# STM32_SCHEMATIC.net
KiCad netlist of a schematic drawn in Altium Designer
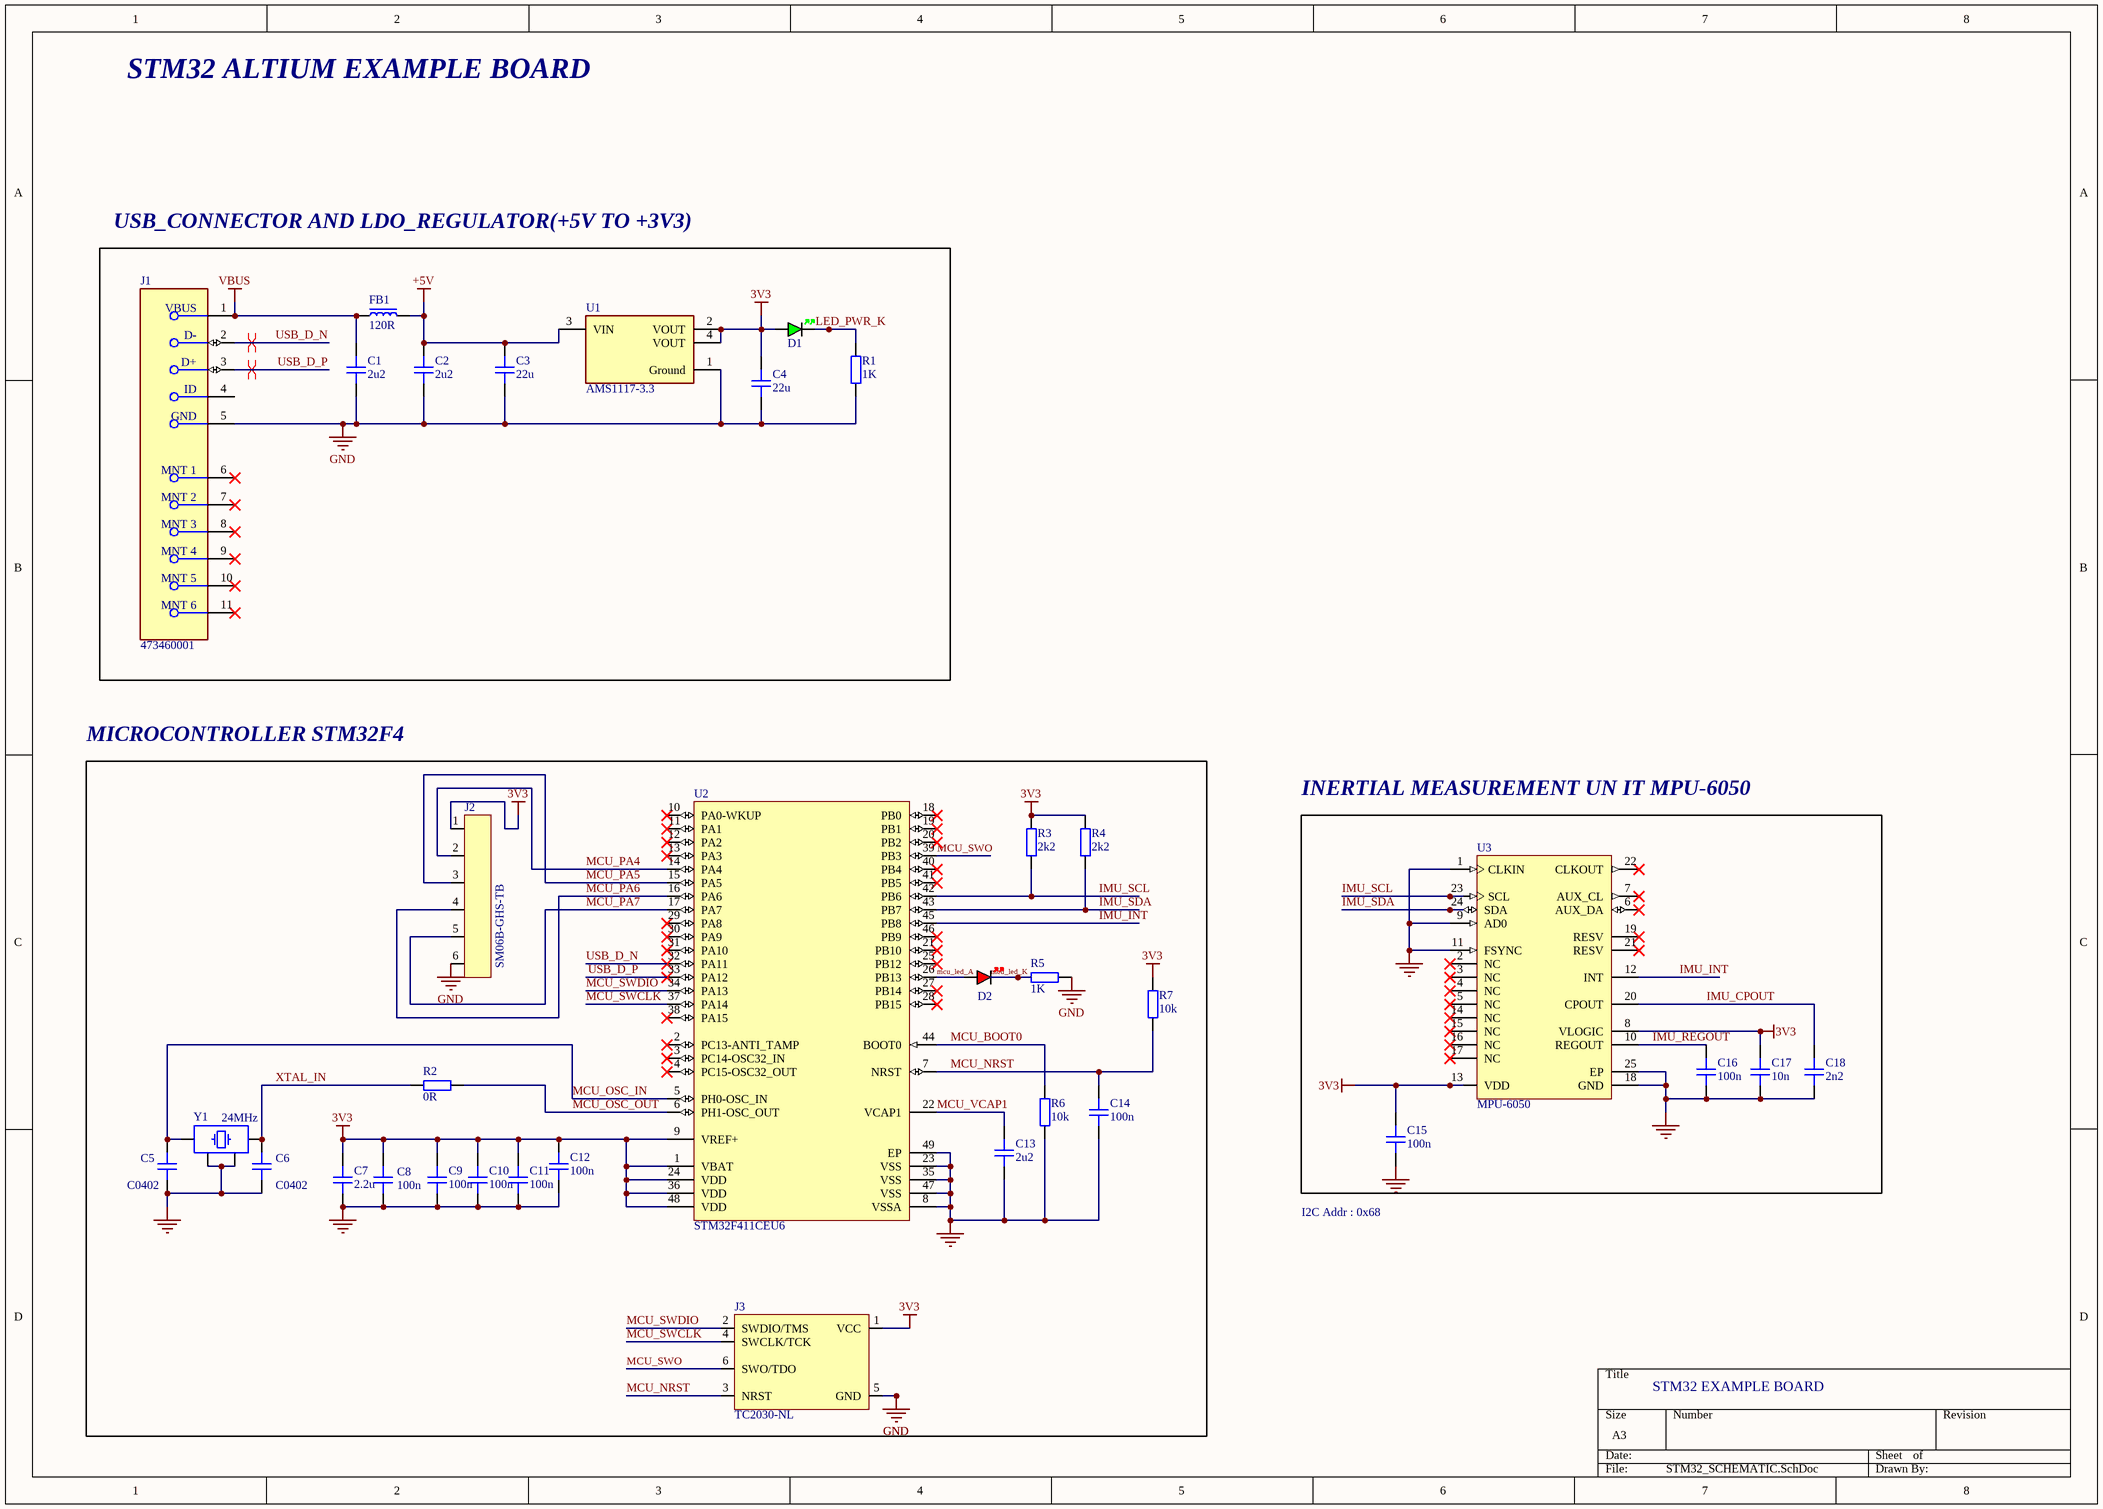
[diagram p0: STM32_SCHEMATIC.SchDoc]

(export (version "E")
  (design (tool "Eeschema 10.0.6"))
  (components
    (comp (ref "C1")
      (value "2u2")
      (footprint "CAP_0402")
      (description "Capacitor SMD 0402")
      (libsource (lib "Schematic-Lib-PhilsLab") (part "CAP_0402"))
    )
    (comp (ref "C2")
      (value "2u2")
      (footprint "CAP_0402")
      (description "Capacitor SMD 0402")
      (libsource (lib "Schematic-Lib-PhilsLab") (part "CAP_0402"))
    )
    (comp (ref "C3")
      (value "22u")
      (footprint "CAP_0805")
      (description "Capacitor SMD 0805")
      (libsource (lib "Schematic-Lib-PhilsLab") (part "CAP_0805"))
    )
    (comp (ref "C4")
      (value "22u")
      (footprint "CAP_0805")
      (description "Capacitor SMD 0805")
      (libsource (lib "Schematic-Lib-PhilsLab") (part "CAP_0805"))
    )
    (comp (ref "C5")
      (value "C0402")
      (footprint "CAP_0402")
      (description "Capacitor SMD 0402")
      (libsource (lib "Schematic-Lib-PhilsLab") (part "CAP_0402"))
    )
    (comp (ref "C6")
      (value "C0402")
      (footprint "CAP_0402")
      (description "Capacitor SMD 0402")
      (libsource (lib "Schematic-Lib-PhilsLab") (part "CAP_0402"))
    )
    (comp (ref "C7")
      (value "2.2u")
      (footprint "CAP_0603")
      (description "Capacitor SMD 0603")
      (libsource (lib "Schematic-Lib-PhilsLab") (part "CAP_0603"))
    )
    (comp (ref "C8")
      (value "100n")
      (footprint "CAP_0402")
      (description "Capacitor SMD 0402")
      (libsource (lib "Schematic-Lib-PhilsLab") (part "CAP_0402"))
    )
    (comp (ref "C9")
      (value "100n")
      (footprint "CAP_0402")
      (description "Capacitor SMD 0402")
      (libsource (lib "Schematic-Lib-PhilsLab") (part "CAP_0402"))
    )
    (comp (ref "C10")
      (value "100n")
      (footprint "CAP_0402")
      (description "Capacitor SMD 0402")
      (libsource (lib "Schematic-Lib-PhilsLab") (part "CAP_0402"))
    )
    (comp (ref "C11")
      (value "100n")
      (footprint "CAP_0402")
      (description "Capacitor SMD 0402")
      (libsource (lib "Schematic-Lib-PhilsLab") (part "CAP_0402"))
    )
    (comp (ref "C12")
      (value "100n")
      (footprint "CAP_0402")
      (description "Capacitor SMD 0402")
      (libsource (lib "Schematic-Lib-PhilsLab") (part "CAP_0402"))
    )
    (comp (ref "C13")
      (value "2u2")
      (footprint "CAP_0603")
      (description "Capacitor SMD 0603")
      (libsource (lib "Schematic-Lib-PhilsLab") (part "CAP_0603"))
    )
    (comp (ref "C14")
      (value "100n")
      (footprint "CAP_0402")
      (description "Capacitor SMD 0402")
      (libsource (lib "Schematic-Lib-PhilsLab") (part "CAP_0402"))
    )
    (comp (ref "C15")
      (value "100n")
      (footprint "CAP_0402")
      (description "Capacitor SMD 0402")
      (libsource (lib "Schematic-Lib-PhilsLab") (part "CAP_0402"))
    )
    (comp (ref "C16")
      (value "100n")
      (footprint "CAP_0402")
      (description "Capacitor SMD 0402")
      (libsource (lib "Schematic-Lib-PhilsLab") (part "CAP_0402"))
    )
    (comp (ref "C17")
      (value "10n")
      (footprint "CAP_0402")
      (description "Capacitor SMD 0402")
      (libsource (lib "Schematic-Lib-PhilsLab") (part "CAP_0402"))
    )
    (comp (ref "C18")
      (value "2n2")
      (footprint "CAP_0402")
      (description "Capacitor SMD 0402")
      (libsource (lib "Schematic-Lib-PhilsLab") (part "CAP_0402"))
    )
    (comp (ref "D1")
      (value "GREEN")
      (footprint "LED_0402_GREEN")
      (description "LED 0402 GREEN SMD")
      (libsource (lib "Schematic-Lib-PhilsLab") (part "LED_0402_GREEN"))
    )
    (comp (ref "D2")
      (value "RED")
      (footprint "LED_0402_RED")
      (description "LED 0402 RED SMD")
      (libsource (lib "Schematic-Lib-PhilsLab") (part "LED_0402_RED"))
    )
    (comp (ref "FB1")
      (value "120R")
      (footprint "FB_0603")
      (description "Ferrite Bead SMD 0603")
      (libsource (lib "Schematic-Lib-PhilsLab") (part "FB_0603"))
    )
    (comp (ref "J1")
      (value "473460001")
      (footprint "FP-473460001-MFG")
      (description "USB - micro B USB 2.0 Receptacle Connector 5 Position Surface Mount, Right Angle")
      (fields (field (name "OCTOPART") "https://octopart.com/47346-0001-molex-7164928"))
      (libsource (lib "Altium Content Vault") (part "53ae1f1d9b557310b43ca686e5bb76a"))
    )
    (comp (ref "J2")
      (value "SM06B-GHS-TB")
      (footprint "SM06B-GHS-TB")
      (description "Header Connector 6 Position 1.25MM Pitch SMD Horizontal JST GH")
      (fields (field (name "MANUFACTURER") "JST"))
      (libsource (lib "Schematic-Lib-PhilsLab") (part "SM06B-GHS-TB"))
    )
    (comp (ref "J3")
      (value "TC2030-NL")
      (footprint "TC2030-NL-FP")
      (description "Tag-Connect No-Solder SWD Debug Connector (No Legs) DO NOT PLACE")
      (fields
        (field (name "MANUFACTURER") "Tag-Connect")
        (field (name "MANUFACTURER PART NUMBER") "TC2030-NL-FP")
      )
      (libsource (lib "Schematic-Lib-PhilsLab") (part "TC2030-NL"))
    )
    (comp (ref "R1")
      (value "1K")
      (footprint "RES_0402")
      (description "Resistor SMD 0402")
      (libsource (lib "Schematic-Lib-PhilsLab") (part "RES_0402"))
    )
    (comp (ref "R2")
      (value "0R")
      (footprint "RES_0402")
      (description "Resistor SMD 0402")
      (libsource (lib "Schematic-Lib-PhilsLab") (part "RES_0402"))
    )
    (comp (ref "R3")
      (value "2k2")
      (footprint "RES_0402")
      (description "Resistor SMD 0402")
      (libsource (lib "Schematic-Lib-PhilsLab") (part "RES_0402"))
    )
    (comp (ref "R4")
      (value "2k2")
      (footprint "RES_0402")
      (description "Resistor SMD 0402")
      (libsource (lib "Schematic-Lib-PhilsLab") (part "RES_0402"))
    )
    (comp (ref "R5")
      (value "1K")
      (footprint "RES_0402")
      (description "Resistor SMD 0402")
      (libsource (lib "Schematic-Lib-PhilsLab") (part "RES_0402"))
    )
    (comp (ref "R6")
      (value "10k")
      (footprint "RES_0402")
      (description "Resistor SMD 0402")
      (libsource (lib "Schematic-Lib-PhilsLab") (part "RES_0402"))
    )
    (comp (ref "R7")
      (value "10k")
      (footprint "RES_0402")
      (description "Resistor SMD 0402")
      (libsource (lib "Schematic-Lib-PhilsLab") (part "RES_0402"))
    )
    (comp (ref "U1")
      (value "AMS1117-3.3")
      (footprint "FP-AMS1117-IPC_C")
      (description "LDO Voltage Regulators 1A, 3.3V")
      (fields
        (field (name "OCTOPART") "https://octopart.com/ams1117-3.3-advanced+monolithic+systems-25899300")
        (field (name "MANUFACTURER") "Advanced Monolithic Systems")
      )
      (libsource (lib "Altium Content Vault") (part "8bdbb5f8e77002000e30dd2845d0354"))
    )
    (comp (ref "U2")
      (value "STM32F411CEU6")
      (footprint "STM-UFQFPN48_L")
      (libsource (lib "Altium Content Vault") (part "MC-ARM-STM32F411-UFQFPN48"))
    )
    (comp (ref "U3")
      (value "MPU-6050")
      (footprint "IS-QFN-24_V")
      (fields (field (name "MANUFACTURER") "InvenSense"))
      (libsource (lib "Altium Content Vault") (part "IS-MPU-6050-QFN-24"))
    )
    (comp (ref "Y1")
      (value "24MHz")
      (footprint "XTAL_3225")
      (description "Crystal SMD 24MHz 10PPM 7pF 3225")
      (fields
        (field (name "MANUFACTURER") "Epson")
        (field (name "MANUFACTURER PART NUMBER") "TSX-3225 24.0000MF15X-AC")
      )
      (libsource (lib "Schematic-Lib-PhilsLab") (part "TSX-3225_24.0000MF15X-AC"))
    )
  )
  (nets
    (net (code "1") (name "+5V") (class "Default")
      (node (ref "C2") (pin "1") (pinfunction "1_1") (pintype "passive"))
      (node (ref "C3") (pin "2") (pinfunction "2_2") (pintype "passive"))
      (node (ref "FB1") (pin "2") (pinfunction "2_2") (pintype "passive"))
      (node (ref "U1") (pin "3") (pinfunction "VIN_3") (pintype "power_in"))
    )
    (net (code "2") (name "/IMU_CPOUT") (class "Default")
      (node (ref "C18") (pin "1") (pinfunction "1_1") (pintype "passive"))
      (node (ref "U3") (pin "20") (pinfunction "CPOUT_20") (pintype "passive"))
    )
    (net (code "3") (name "/IMU_INT") (class "Default")
      (node (ref "U2") (pin "45") (pinfunction "PB8_45") (pintype "bidirectional"))
      (node (ref "U3") (pin "12") (pinfunction "INT_12") (pintype "open_collector"))
    )
    (net (code "4") (name "/IMU_REGOUT") (class "Default")
      (node (ref "C16") (pin "1") (pinfunction "1_1") (pintype "passive"))
      (node (ref "U3") (pin "10") (pinfunction "REGOUT_10") (pintype "passive"))
    )
    (net (code "5") (name "/IMU_SCL") (class "Default")
      (node (ref "R3") (pin "1") (pinfunction "1_1") (pintype "passive"))
      (node (ref "U2") (pin "42") (pinfunction "PB6_42") (pintype "bidirectional"))
      (node (ref "U3") (pin "23") (pinfunction "SCL_23") (pintype "input"))
    )
    (net (code "6") (name "/IMU_SDA") (class "Default")
      (node (ref "R4") (pin "1") (pinfunction "1_1") (pintype "passive"))
      (node (ref "U2") (pin "43") (pinfunction "PB7_43") (pintype "bidirectional"))
      (node (ref "U3") (pin "24") (pinfunction "SDA_24") (pintype "bidirectional"))
    )
    (net (code "7") (name "/LED_PWR_K") (class "Default")
      (node (ref "D1") (pin "K") (pinfunction "K_K") (pintype "passive"))
      (node (ref "R1") (pin "2") (pinfunction "2_2") (pintype "passive"))
    )
    (net (code "8") (name "/MCU_BOOT0") (class "Default")
      (node (ref "R6") (pin "1") (pinfunction "1_1") (pintype "passive"))
      (node (ref "U2") (pin "44") (pinfunction "BOOT0_44") (pintype "input"))
    )
    (net (code "9") (name "/MCU_NRST") (class "Default")
      (node (ref "C14") (pin "1") (pinfunction "1_1") (pintype "passive"))
      (node (ref "J3") (pin "3") (pinfunction "NRST_3") (pintype "passive"))
      (node (ref "R7") (pin "2") (pinfunction "2_2") (pintype "passive"))
      (node (ref "U2") (pin "7") (pinfunction "NRST_7") (pintype "bidirectional"))
    )
    (net (code "10") (name "/MCU_OSC_IN") (class "Default")
      (node (ref "C5") (pin "1") (pinfunction "1_1") (pintype "passive"))
      (node (ref "U2") (pin "5") (pinfunction "PH0-OSC_IN_5") (pintype "bidirectional"))
      (node (ref "Y1") (pin "1") (pinfunction "1_1") (pintype "passive"))
    )
    (net (code "11") (name "/MCU_OSC_OUT") (class "Default")
      (node (ref "R2") (pin "1") (pinfunction "1_1") (pintype "passive"))
      (node (ref "U2") (pin "6") (pinfunction "PH1-OSC_OUT_6") (pintype "bidirectional"))
    )
    (net (code "12") (name "/MCU_PA4") (class "Default")
      (node (ref "J2") (pin "2") (pinfunction "2_2") (pintype "passive"))
      (node (ref "U2") (pin "14") (pinfunction "PA4_14") (pintype "bidirectional"))
    )
    (net (code "13") (name "/MCU_PA5") (class "Default")
      (node (ref "J2") (pin "3") (pinfunction "3_3") (pintype "passive"))
      (node (ref "U2") (pin "15") (pinfunction "PA5_15") (pintype "bidirectional"))
    )
    (net (code "14") (name "/MCU_PA6") (class "Default")
      (node (ref "J2") (pin "4") (pinfunction "4_4") (pintype "passive"))
      (node (ref "U2") (pin "16") (pinfunction "PA6_16") (pintype "bidirectional"))
    )
    (net (code "15") (name "/MCU_PA7") (class "Default")
      (node (ref "J2") (pin "5") (pinfunction "5_5") (pintype "passive"))
      (node (ref "U2") (pin "17") (pinfunction "PA7_17") (pintype "bidirectional"))
    )
    (net (code "16") (name "/MCU_SWCLK") (class "Default")
      (node (ref "J3") (pin "4") (pinfunction "SWCLK/TCK_4") (pintype "passive"))
      (node (ref "U2") (pin "37") (pinfunction "PA14_37") (pintype "bidirectional"))
    )
    (net (code "17") (name "/MCU_SWDIO") (class "Default")
      (node (ref "J3") (pin "2") (pinfunction "SWDIO/TMS_2") (pintype "passive"))
      (node (ref "U2") (pin "34") (pinfunction "PA13_34") (pintype "bidirectional"))
    )
    (net (code "18") (name "/MCU_SWO") (class "Default")
      (node (ref "J3") (pin "6") (pinfunction "SWO/TDO_6") (pintype "passive"))
      (node (ref "U2") (pin "39") (pinfunction "PB3_39") (pintype "bidirectional"))
    )
    (net (code "19") (name "/MCU_VCAP1") (class "Default")
      (node (ref "C13") (pin "1") (pinfunction "1_1") (pintype "passive"))
      (node (ref "U2") (pin "22") (pinfunction "VCAP1_22") (pintype "passive"))
    )
    (net (code "20") (name "/USB_D_N") (class "Default")
      (node (ref "J1") (pin "2") (pinfunction "D-_2") (pintype "bidirectional"))
      (node (ref "U2") (pin "32") (pinfunction "PA11_32") (pintype "bidirectional"))
    )
    (net (code "21") (name "/USB_D_P") (class "Default")
      (node (ref "J1") (pin "3") (pinfunction "D+_3") (pintype "bidirectional"))
      (node (ref "U2") (pin "33") (pinfunction "PA12_33") (pintype "bidirectional"))
    )
    (net (code "22") (name "/XTAL_IN") (class "Default")
      (node (ref "C6") (pin "1") (pinfunction "1_1") (pintype "passive"))
      (node (ref "R2") (pin "2") (pinfunction "2_2") (pintype "passive"))
      (node (ref "Y1") (pin "3") (pinfunction "3_3") (pintype "passive"))
    )
    (net (code "23") (name "/mcu_led_A") (class "Default")
      (node (ref "D2") (pin "A") (pinfunction "A_A") (pintype "passive"))
      (node (ref "U2") (pin "26") (pinfunction "PB13_26") (pintype "bidirectional"))
    )
    (net (code "24") (name "/mcu_led_K") (class "Default")
      (node (ref "D2") (pin "K") (pinfunction "K_K") (pintype "passive"))
      (node (ref "R5") (pin "2") (pinfunction "2_2") (pintype "passive"))
    )
    (net (code "25") (name "3V3") (class "Default")
      (node (ref "C10") (pin "1") (pinfunction "1_1") (pintype "passive"))
      (node (ref "C11") (pin "1") (pinfunction "1_1") (pintype "passive"))
      (node (ref "C12") (pin "1") (pinfunction "1_1") (pintype "passive"))
      (node (ref "C15") (pin "1") (pinfunction "1_1") (pintype "passive"))
      (node (ref "C17") (pin "1") (pinfunction "1_1") (pintype "passive"))
      (node (ref "C4") (pin "2") (pinfunction "2_2") (pintype "passive"))
      (node (ref "C7") (pin "1") (pinfunction "1_1") (pintype "passive"))
      (node (ref "C8") (pin "1") (pinfunction "1_1") (pintype "passive"))
      (node (ref "C9") (pin "1") (pinfunction "1_1") (pintype "passive"))
      (node (ref "D1") (pin "A") (pinfunction "A_A") (pintype "passive"))
      (node (ref "J2") (pin "1") (pinfunction "1_1") (pintype "passive"))
      (node (ref "J3") (pin "1") (pinfunction "VCC_1") (pintype "passive"))
      (node (ref "R3") (pin "2") (pinfunction "2_2") (pintype "passive"))
      (node (ref "R4") (pin "2") (pinfunction "2_2") (pintype "passive"))
      (node (ref "R7") (pin "1") (pinfunction "1_1") (pintype "passive"))
      (node (ref "U1") (pin "2") (pinfunction "VOUT_2") (pintype "passive"))
      (node (ref "U1") (pin "4") (pinfunction "VOUT_4") (pintype "passive"))
      (node (ref "U2") (pin "1") (pinfunction "VBAT_1") (pintype "power_in"))
      (node (ref "U2") (pin "24") (pinfunction "VDD_24") (pintype "power_in"))
      (node (ref "U2") (pin "36") (pinfunction "VDD_36") (pintype "power_in"))
      (node (ref "U2") (pin "48") (pinfunction "VDD_48") (pintype "power_in"))
      (node (ref "U2") (pin "9") (pinfunction "VREF+_9") (pintype "power_in"))
      (node (ref "U3") (pin "13") (pinfunction "VDD_13") (pintype "power_in"))
      (node (ref "U3") (pin "8") (pinfunction "VLOGIC_8") (pintype "power_in"))
    )
    (net (code "26") (name "GND") (class "Default")
      (node (ref "C1") (pin "2") (pinfunction "2_2") (pintype "passive"))
      (node (ref "C10") (pin "2") (pinfunction "2_2") (pintype "passive"))
      (node (ref "C11") (pin "2") (pinfunction "2_2") (pintype "passive"))
      (node (ref "C12") (pin "2") (pinfunction "2_2") (pintype "passive"))
      (node (ref "C13") (pin "2") (pinfunction "2_2") (pintype "passive"))
      (node (ref "C14") (pin "2") (pinfunction "2_2") (pintype "passive"))
      (node (ref "C15") (pin "2") (pinfunction "2_2") (pintype "passive"))
      (node (ref "C16") (pin "2") (pinfunction "2_2") (pintype "passive"))
      (node (ref "C17") (pin "2") (pinfunction "2_2") (pintype "passive"))
      (node (ref "C18") (pin "2") (pinfunction "2_2") (pintype "passive"))
      (node (ref "C2") (pin "2") (pinfunction "2_2") (pintype "passive"))
      (node (ref "C3") (pin "1") (pinfunction "1_1") (pintype "passive"))
      (node (ref "C4") (pin "1") (pinfunction "1_1") (pintype "passive"))
      (node (ref "C5") (pin "2") (pinfunction "2_2") (pintype "passive"))
      (node (ref "C6") (pin "2") (pinfunction "2_2") (pintype "passive"))
      (node (ref "C7") (pin "2") (pinfunction "2_2") (pintype "passive"))
      (node (ref "C8") (pin "2") (pinfunction "2_2") (pintype "passive"))
      (node (ref "C9") (pin "2") (pinfunction "2_2") (pintype "passive"))
      (node (ref "J1") (pin "5") (pinfunction "GND_5") (pintype "power_in"))
      (node (ref "J2") (pin "6") (pinfunction "6_6") (pintype "passive"))
      (node (ref "J3") (pin "5") (pinfunction "GND_5") (pintype "passive"))
      (node (ref "R1") (pin "1") (pinfunction "1_1") (pintype "passive"))
      (node (ref "R5") (pin "1") (pinfunction "1_1") (pintype "passive"))
      (node (ref "R6") (pin "2") (pinfunction "2_2") (pintype "passive"))
      (node (ref "U1") (pin "1") (pinfunction "Ground_1") (pintype "power_in"))
      (node (ref "U2") (pin "23") (pinfunction "VSS_23") (pintype "power_in"))
      (node (ref "U2") (pin "35") (pinfunction "VSS_35") (pintype "power_in"))
      (node (ref "U2") (pin "47") (pinfunction "VSS_47") (pintype "power_in"))
      (node (ref "U2") (pin "49") (pinfunction "EP_49") (pintype "power_in"))
      (node (ref "U2") (pin "8") (pinfunction "VSSA_8") (pintype "power_in"))
      (node (ref "U3") (pin "1") (pinfunction "CLKIN_1") (pintype "input"))
      (node (ref "U3") (pin "11") (pinfunction "FSYNC_11") (pintype "input"))
      (node (ref "U3") (pin "18") (pinfunction "GND_18") (pintype "power_in"))
      (node (ref "U3") (pin "25") (pinfunction "EP_25") (pintype "power_in"))
      (node (ref "U3") (pin "9") (pinfunction "AD0_9") (pintype "input"))
      (node (ref "Y1") (pin "2") (pinfunction "2_2") (pintype "passive"))
      (node (ref "Y1") (pin "4") (pinfunction "4_4") (pintype "passive"))
    )
    (net (code "27") (name "VBUS") (class "Default")
      (node (ref "C1") (pin "1") (pinfunction "1_1") (pintype "passive"))
      (node (ref "FB1") (pin "1") (pinfunction "1_1") (pintype "passive"))
      (node (ref "J1") (pin "1") (pinfunction "VBUS_1") (pintype "power_in"))
    )
    (net (code "28") (name "unconnected-(J1-ID-Pad4)") (class "Default")
      (node (ref "J1") (pin "4") (pinfunction "ID_4") (pintype "passive"))
    )
    (net (code "29") (name "unconnected-(J1-MNT_1-Pad6)") (class "Default")
      (node (ref "J1") (pin "6") (pinfunction "MNT_1_6") (pintype "passive+no_connect"))
    )
    (net (code "30") (name "unconnected-(J1-MNT_2-Pad7)") (class "Default")
      (node (ref "J1") (pin "7") (pinfunction "MNT_2_7") (pintype "passive+no_connect"))
    )
    (net (code "31") (name "unconnected-(J1-MNT_3-Pad8)") (class "Default")
      (node (ref "J1") (pin "8") (pinfunction "MNT_3_8") (pintype "passive+no_connect"))
    )
    (net (code "32") (name "unconnected-(J1-MNT_4-Pad9)") (class "Default")
      (node (ref "J1") (pin "9") (pinfunction "MNT_4_9") (pintype "passive+no_connect"))
    )
    (net (code "33") (name "unconnected-(J1-MNT_5-Pad10)") (class "Default")
      (node (ref "J1") (pin "10") (pinfunction "MNT_5_10") (pintype "passive+no_connect"))
    )
    (net (code "34") (name "unconnected-(J1-MNT_6-Pad11)") (class "Default")
      (node (ref "J1") (pin "11") (pinfunction "MNT_6_11") (pintype "passive+no_connect"))
    )
    (net (code "35") (name "unconnected-(U2-PA0-WKUP-Pad10)") (class "Default")
      (node (ref "U2") (pin "10") (pinfunction "PA0-WKUP_10") (pintype "bidirectional+no_connect"))
    )
    (net (code "36") (name "unconnected-(U2-PA1-Pad11)") (class "Default")
      (node (ref "U2") (pin "11") (pinfunction "PA1_11") (pintype "bidirectional+no_connect"))
    )
    (net (code "37") (name "unconnected-(U2-PA2-Pad12)") (class "Default")
      (node (ref "U2") (pin "12") (pinfunction "PA2_12") (pintype "bidirectional+no_connect"))
    )
    (net (code "38") (name "unconnected-(U2-PA3-Pad13)") (class "Default")
      (node (ref "U2") (pin "13") (pinfunction "PA3_13") (pintype "bidirectional+no_connect"))
    )
    (net (code "39") (name "unconnected-(U2-PA8-Pad29)") (class "Default")
      (node (ref "U2") (pin "29") (pinfunction "PA8_29") (pintype "bidirectional+no_connect"))
    )
    (net (code "40") (name "unconnected-(U2-PA9-Pad30)") (class "Default")
      (node (ref "U2") (pin "30") (pinfunction "PA9_30") (pintype "bidirectional+no_connect"))
    )
    (net (code "41") (name "unconnected-(U2-PA10-Pad31)") (class "Default")
      (node (ref "U2") (pin "31") (pinfunction "PA10_31") (pintype "bidirectional+no_connect"))
    )
    (net (code "42") (name "unconnected-(U2-PA15-Pad38)") (class "Default")
      (node (ref "U2") (pin "38") (pinfunction "PA15_38") (pintype "bidirectional+no_connect"))
    )
    (net (code "43") (name "unconnected-(U2-PB0-Pad18)") (class "Default")
      (node (ref "U2") (pin "18") (pinfunction "PB0_18") (pintype "bidirectional+no_connect"))
    )
    (net (code "44") (name "unconnected-(U2-PB1-Pad19)") (class "Default")
      (node (ref "U2") (pin "19") (pinfunction "PB1_19") (pintype "bidirectional+no_connect"))
    )
    (net (code "45") (name "unconnected-(U2-PB2-Pad20)") (class "Default")
      (node (ref "U2") (pin "20") (pinfunction "PB2_20") (pintype "bidirectional+no_connect"))
    )
    (net (code "46") (name "unconnected-(U2-PB4-Pad40)") (class "Default")
      (node (ref "U2") (pin "40") (pinfunction "PB4_40") (pintype "bidirectional+no_connect"))
    )
    (net (code "47") (name "unconnected-(U2-PB5-Pad41)") (class "Default")
      (node (ref "U2") (pin "41") (pinfunction "PB5_41") (pintype "bidirectional+no_connect"))
    )
    (net (code "48") (name "unconnected-(U2-PB9-Pad46)") (class "Default")
      (node (ref "U2") (pin "46") (pinfunction "PB9_46") (pintype "bidirectional+no_connect"))
    )
    (net (code "49") (name "unconnected-(U2-PB10-Pad21)") (class "Default")
      (node (ref "U2") (pin "21") (pinfunction "PB10_21") (pintype "bidirectional+no_connect"))
    )
    (net (code "50") (name "unconnected-(U2-PB12-Pad25)") (class "Default")
      (node (ref "U2") (pin "25") (pinfunction "PB12_25") (pintype "bidirectional+no_connect"))
    )
    (net (code "51") (name "unconnected-(U2-PB14-Pad27)") (class "Default")
      (node (ref "U2") (pin "27") (pinfunction "PB14_27") (pintype "bidirectional+no_connect"))
    )
    (net (code "52") (name "unconnected-(U2-PB15-Pad28)") (class "Default")
      (node (ref "U2") (pin "28") (pinfunction "PB15_28") (pintype "bidirectional+no_connect"))
    )
    (net (code "53") (name "unconnected-(U2-PC13-ANTI_TAMP-Pad2)") (class "Default")
      (node (ref "U2") (pin "2") (pinfunction "PC13-ANTI_TAMP_2") (pintype "bidirectional+no_connect"))
    )
    (net (code "54") (name "unconnected-(U2-PC14-OSC32_IN-Pad3)") (class "Default")
      (node (ref "U2") (pin "3") (pinfunction "PC14-OSC32_IN_3") (pintype "bidirectional+no_connect"))
    )
    (net (code "55") (name "unconnected-(U2-PC15-OSC32_OUT-Pad4)") (class "Default")
      (node (ref "U2") (pin "4") (pinfunction "PC15-OSC32_OUT_4") (pintype "bidirectional+no_connect"))
    )
    (net (code "56") (name "unconnected-(U3-AUX_CL-Pad7)") (class "Default")
      (node (ref "U3") (pin "7") (pinfunction "AUX_CL_7") (pintype "output+no_connect"))
    )
    (net (code "57") (name "unconnected-(U3-AUX_DA-Pad6)") (class "Default")
      (node (ref "U3") (pin "6") (pinfunction "AUX_DA_6") (pintype "bidirectional+no_connect"))
    )
    (net (code "58") (name "unconnected-(U3-CLKOUT-Pad22)") (class "Default")
      (node (ref "U3") (pin "22") (pinfunction "CLKOUT_22") (pintype "output+no_connect"))
    )
    (net (code "59") (name "unconnected-(U3-NC-Pad2)") (class "Default")
      (node (ref "U3") (pin "2") (pinfunction "NC_2") (pintype "passive+no_connect"))
    )
    (net (code "60") (name "unconnected-(U3-NC-Pad3)") (class "Default")
      (node (ref "U3") (pin "3") (pinfunction "NC_3") (pintype "passive+no_connect"))
    )
    (net (code "61") (name "unconnected-(U3-NC-Pad4)") (class "Default")
      (node (ref "U3") (pin "4") (pinfunction "NC_4") (pintype "passive+no_connect"))
    )
    (net (code "62") (name "unconnected-(U3-NC-Pad5)") (class "Default")
      (node (ref "U3") (pin "5") (pinfunction "NC_5") (pintype "passive+no_connect"))
    )
    (net (code "63") (name "unconnected-(U3-NC-Pad14)") (class "Default")
      (node (ref "U3") (pin "14") (pinfunction "NC_14") (pintype "passive+no_connect"))
    )
    (net (code "64") (name "unconnected-(U3-NC-Pad15)") (class "Default")
      (node (ref "U3") (pin "15") (pinfunction "NC_15") (pintype "passive+no_connect"))
    )
    (net (code "65") (name "unconnected-(U3-NC-Pad16)") (class "Default")
      (node (ref "U3") (pin "16") (pinfunction "NC_16") (pintype "passive+no_connect"))
    )
    (net (code "66") (name "unconnected-(U3-NC-Pad17)") (class "Default")
      (node (ref "U3") (pin "17") (pinfunction "NC_17") (pintype "passive+no_connect"))
    )
    (net (code "67") (name "unconnected-(U3-RESV-Pad19)") (class "Default")
      (node (ref "U3") (pin "19") (pinfunction "RESV_19") (pintype "passive+no_connect"))
    )
    (net (code "68") (name "unconnected-(U3-RESV-Pad21)") (class "Default")
      (node (ref "U3") (pin "21") (pinfunction "RESV_21") (pintype "passive+no_connect"))
    )
  )
)
